# power_distribution_board.net
KiCad netlist of a schematic drawn in EAGLE
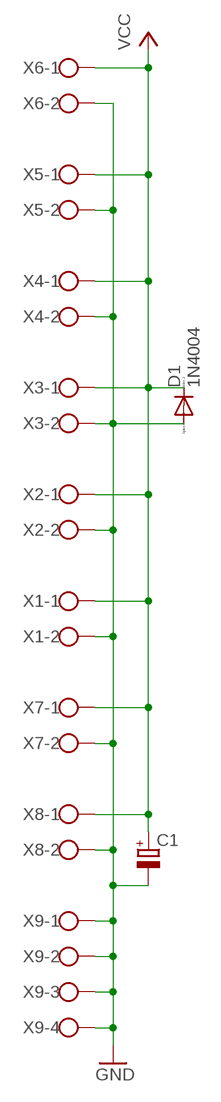
[diagram p0: schematic, sheet 1]

(export (version "E")
  (design (tool "Eeschema 10.0.6"))
  (components
    (comp (ref "C1")
      (value "CPOL-EUE5-10.5")
      (footprint "eagle-import:E5-10,5")
      (libsource (lib "eagle-import") (part "CPOL-EUE5-10.5"))
    )
    (comp (ref "D1")
      (value "1N4004")
      (footprint "eagle-import:DO41-10")
      (libsource (lib "eagle-import") (part "1N4004"))
    )
    (comp (ref "X1")
      (value "W237-102")
      (footprint "eagle-import:W237-102")
      (fields (field (name "MPN") "237-102"))
      (libsource (lib "eagle-import") (part "W237-102"))
    )
    (comp (ref "X2")
      (value "W237-102")
      (footprint "eagle-import:W237-102")
      (fields (field (name "MPN") "237-102"))
      (libsource (lib "eagle-import") (part "W237-102"))
    )
    (comp (ref "X3")
      (value "W237-102")
      (footprint "eagle-import:W237-102")
      (fields (field (name "MPN") "237-102"))
      (libsource (lib "eagle-import") (part "W237-102"))
    )
    (comp (ref "X4")
      (value "W237-102")
      (footprint "eagle-import:W237-102")
      (fields (field (name "MPN") "237-102"))
      (libsource (lib "eagle-import") (part "W237-102"))
    )
    (comp (ref "X5")
      (value "W237-102")
      (footprint "eagle-import:W237-102")
      (fields (field (name "MPN") "237-102"))
      (libsource (lib "eagle-import") (part "W237-102"))
    )
    (comp (ref "X6")
      (value "W237-102")
      (footprint "eagle-import:W237-102")
      (fields (field (name "MPN") "237-102"))
      (libsource (lib "eagle-import") (part "W237-102"))
    )
    (comp (ref "X7")
      (value "W237-102")
      (footprint "eagle-import:W237-102")
      (fields (field (name "MPN") "237-102"))
      (libsource (lib "eagle-import") (part "W237-102"))
    )
    (comp (ref "X8")
      (value "W237-102")
      (footprint "eagle-import:W237-102")
      (fields (field (name "MPN") "237-102"))
      (libsource (lib "eagle-import") (part "W237-102"))
    )
    (comp (ref "X9")
      (value "W237-4")
      (footprint "eagle-import:W237-4")
      (libsource (lib "eagle-import") (part "W237-4"))
    )
  )
  (nets
    (net (code "1") (name "GND") (class "Default")
      (node (ref "C1") (pin "-") (pinfunction "-_-") (pintype "passive"))
      (node (ref "D1") (pin "A") (pinfunction "A_A") (pintype "passive"))
      (node (ref "X1") (pin "2") (pinfunction "KL_2") (pintype "passive"))
      (node (ref "X2") (pin "2") (pinfunction "KL_2") (pintype "passive"))
      (node (ref "X3") (pin "2") (pinfunction "KL_2") (pintype "passive"))
      (node (ref "X4") (pin "2") (pinfunction "KL_2") (pintype "passive"))
      (node (ref "X5") (pin "2") (pinfunction "KL_2") (pintype "passive"))
      (node (ref "X6") (pin "2") (pinfunction "KL_2") (pintype "passive"))
      (node (ref "X7") (pin "2") (pinfunction "KL_2") (pintype "passive"))
      (node (ref "X8") (pin "2") (pinfunction "KL_2") (pintype "passive"))
      (node (ref "X9") (pin "1") (pinfunction "KL_1") (pintype "passive"))
      (node (ref "X9") (pin "2") (pinfunction "KL_2") (pintype "passive"))
      (node (ref "X9") (pin "3") (pinfunction "KL_3") (pintype "passive"))
      (node (ref "X9") (pin "4") (pinfunction "KL_4") (pintype "passive"))
    )
    (net (code "2") (name "VCC") (class "Default")
      (node (ref "C1") (pin "+") (pinfunction "+_+") (pintype "passive"))
      (node (ref "D1") (pin "C") (pinfunction "C_C") (pintype "passive"))
      (node (ref "X1") (pin "1") (pinfunction "KL_1") (pintype "passive"))
      (node (ref "X2") (pin "1") (pinfunction "KL_1") (pintype "passive"))
      (node (ref "X3") (pin "1") (pinfunction "KL_1") (pintype "passive"))
      (node (ref "X4") (pin "1") (pinfunction "KL_1") (pintype "passive"))
      (node (ref "X5") (pin "1") (pinfunction "KL_1") (pintype "passive"))
      (node (ref "X6") (pin "1") (pinfunction "KL_1") (pintype "passive"))
      (node (ref "X7") (pin "1") (pinfunction "KL_1") (pintype "passive"))
      (node (ref "X8") (pin "1") (pinfunction "KL_1") (pintype "passive"))
    )
  )
)
